# M-LVDS_PHY.net
KiCad netlist of a schematic drawn in Altium Designer
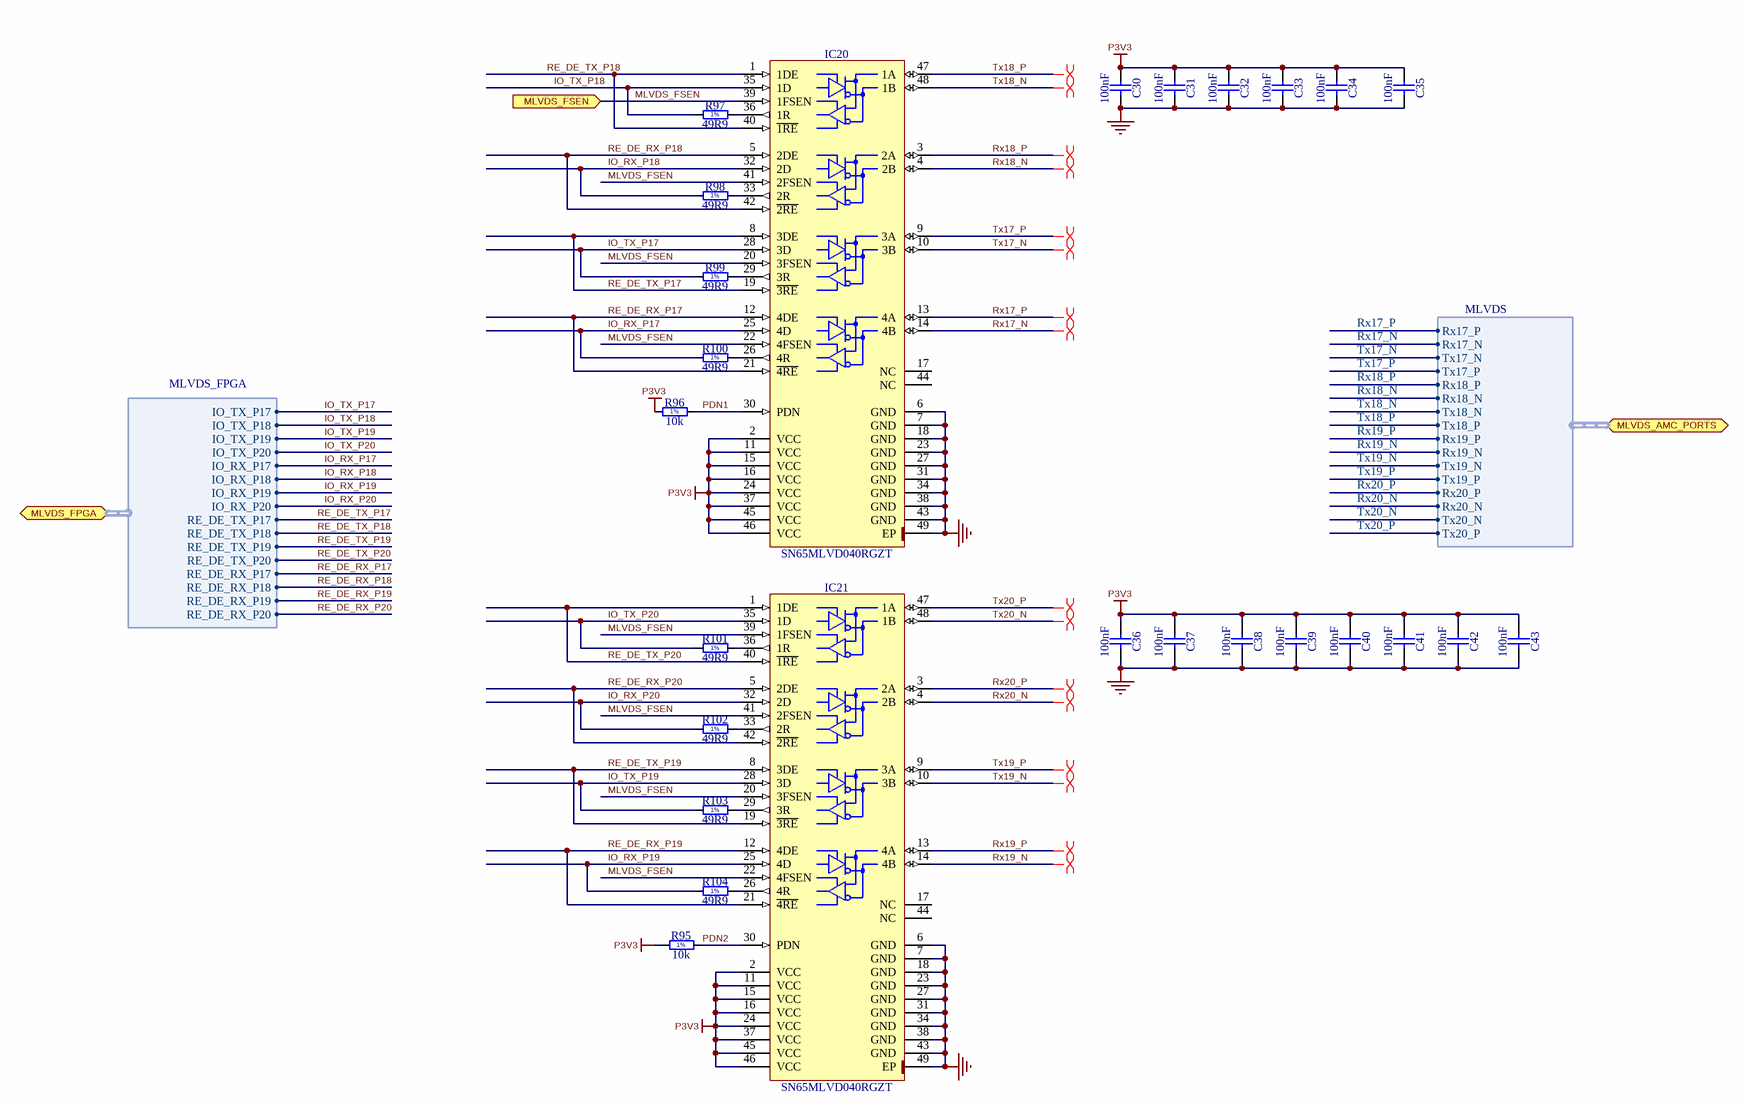
[diagram p0: M-LVDS_PHY.SchDoc]

(export (version "E")
  (design (tool "Eeschema 10.0.6"))
  (components
    (comp (ref "C30")
      (value "100nF")
      (footprint "CAPC0603X33N")
      (description "Non-polarised capacitor")
      (fields
        (field (name "MANUFACTURER PART NUMBER") "CC0201_100NF_6.3V_10%_X5R")
        (field (name "MANUFACTURER") "GENERIC")
        (field (name "AUTHOR") "CERN DEM JLC")
      )
      (libsource (lib "Capacitors") (part "Capacitor - non polarized"))
    )
    (comp (ref "C31")
      (value "100nF")
      (footprint "CAPC0603X33N")
      (description "Non-polarised capacitor")
      (fields
        (field (name "MANUFACTURER PART NUMBER") "CC0201_100NF_6.3V_10%_X5R")
        (field (name "MANUFACTURER") "GENERIC")
        (field (name "AUTHOR") "CERN DEM JLC")
      )
      (libsource (lib "Capacitors") (part "Capacitor - non polarized"))
    )
    (comp (ref "C32")
      (value "100nF")
      (footprint "CAPC0603X33N")
      (description "Non-polarised capacitor")
      (fields
        (field (name "MANUFACTURER PART NUMBER") "CC0201_100NF_6.3V_10%_X5R")
        (field (name "MANUFACTURER") "GENERIC")
        (field (name "AUTHOR") "CERN DEM JLC")
      )
      (libsource (lib "Capacitors") (part "Capacitor - non polarized"))
    )
    (comp (ref "C33")
      (value "100nF")
      (footprint "CAPC0603X33N")
      (description "Non-polarised capacitor")
      (fields
        (field (name "MANUFACTURER PART NUMBER") "CC0201_100NF_6.3V_10%_X5R")
        (field (name "MANUFACTURER") "GENERIC")
        (field (name "AUTHOR") "CERN DEM JLC")
      )
      (libsource (lib "Capacitors") (part "Capacitor - non polarized"))
    )
    (comp (ref "C34")
      (value "100nF")
      (footprint "CAPC0603X33N")
      (description "Non-polarised capacitor")
      (fields
        (field (name "MANUFACTURER PART NUMBER") "CC0201_100NF_6.3V_10%_X5R")
        (field (name "MANUFACTURER") "GENERIC")
        (field (name "AUTHOR") "CERN DEM JLC")
      )
      (libsource (lib "Capacitors") (part "Capacitor - non polarized"))
    )
    (comp (ref "C35")
      (value "100nF")
      (footprint "CAPC0603X33N")
      (description "Non-polarised capacitor")
      (fields
        (field (name "MANUFACTURER PART NUMBER") "CC0201_100NF_6.3V_10%_X5R")
        (field (name "MANUFACTURER") "GENERIC")
        (field (name "AUTHOR") "CERN DEM JLC")
      )
      (libsource (lib "Capacitors") (part "Capacitor - non polarized"))
    )
    (comp (ref "C36")
      (value "100nF")
      (footprint "CAPC0603X33N")
      (description "Non-polarised capacitor")
      (fields
        (field (name "MANUFACTURER PART NUMBER") "CC0201_100NF_6.3V_10%_X5R")
        (field (name "MANUFACTURER") "GENERIC")
        (field (name "AUTHOR") "CERN DEM JLC")
      )
      (libsource (lib "Capacitors") (part "Capacitor - non polarized"))
    )
    (comp (ref "C37")
      (value "100nF")
      (footprint "CAPC0603X33N")
      (description "Non-polarised capacitor")
      (fields
        (field (name "MANUFACTURER PART NUMBER") "CC0201_100NF_6.3V_10%_X5R")
        (field (name "MANUFACTURER") "GENERIC")
        (field (name "AUTHOR") "CERN DEM JLC")
      )
      (libsource (lib "Capacitors") (part "Capacitor - non polarized"))
    )
    (comp (ref "C38")
      (value "100nF")
      (footprint "CAPC0603X33N")
      (description "Non-polarised capacitor")
      (fields
        (field (name "MANUFACTURER PART NUMBER") "CC0201_100NF_6.3V_10%_X5R")
        (field (name "MANUFACTURER") "GENERIC")
        (field (name "AUTHOR") "CERN DEM JLC")
      )
      (libsource (lib "Capacitors") (part "Capacitor - non polarized"))
    )
    (comp (ref "C39")
      (value "100nF")
      (footprint "CAPC0603X33N")
      (description "Non-polarised capacitor")
      (fields
        (field (name "MANUFACTURER PART NUMBER") "CC0201_100NF_6.3V_10%_X5R")
        (field (name "MANUFACTURER") "GENERIC")
        (field (name "AUTHOR") "CERN DEM JLC")
      )
      (libsource (lib "Capacitors") (part "Capacitor - non polarized"))
    )
    (comp (ref "C40")
      (value "100nF")
      (footprint "CAPC0603X33N")
      (description "Non-polarised capacitor")
      (fields
        (field (name "MANUFACTURER PART NUMBER") "CC0201_100NF_6.3V_10%_X5R")
        (field (name "MANUFACTURER") "GENERIC")
        (field (name "AUTHOR") "CERN DEM JLC")
      )
      (libsource (lib "Capacitors") (part "Capacitor - non polarized"))
    )
    (comp (ref "C41")
      (value "100nF")
      (footprint "CAPC0603X33N")
      (description "Non-polarised capacitor")
      (fields
        (field (name "MANUFACTURER PART NUMBER") "CC0201_100NF_6.3V_10%_X5R")
        (field (name "MANUFACTURER") "GENERIC")
        (field (name "AUTHOR") "CERN DEM JLC")
      )
      (libsource (lib "Capacitors") (part "Capacitor - non polarized"))
    )
    (comp (ref "C42")
      (value "100nF")
      (footprint "CAPC0603X33N")
      (description "Non-polarised capacitor")
      (fields
        (field (name "MANUFACTURER PART NUMBER") "CC0201_100NF_6.3V_10%_X5R")
        (field (name "MANUFACTURER") "GENERIC")
        (field (name "AUTHOR") "CERN DEM JLC")
      )
      (libsource (lib "Capacitors") (part "Capacitor - non polarized"))
    )
    (comp (ref "C43")
      (value "100nF")
      (footprint "CAPC0603X33N")
      (description "Non-polarised capacitor")
      (fields
        (field (name "MANUFACTURER PART NUMBER") "CC0201_100NF_6.3V_10%_X5R")
        (field (name "MANUFACTURER") "GENERIC")
        (field (name "AUTHOR") "CERN DEM JLC")
      )
      (libsource (lib "Capacitors") (part "Capacitor - non polarized"))
    )
    (comp (ref "IC20")
      (value "SN65MLVD040RGZT")
      (footprint "QFN50P700X700X100-49N-S420")
      (description "4-Channel Half-Duplex M-LVDS Line Transceiver")
      (fields (field (name "MANUFACTURER") "TEXAS INSTRUMENTS") (field (name "AUTHOR") "CERN DEM JLC"))
      (libsource (lib "ICs And Semiconductors") (part "SN65MLVD040"))
    )
    (comp (ref "IC21")
      (value "SN65MLVD040RGZT")
      (footprint "QFN50P700X700X100-49N-S420")
      (description "4-Channel Half-Duplex M-LVDS Line Transceiver")
      (fields (field (name "MANUFACTURER") "TEXAS INSTRUMENTS") (field (name "AUTHOR") "CERN DEM JLC"))
      (libsource (lib "ICs And Semiconductors") (part "SN65MLVD040"))
    )
    (comp (ref "R95")
      (value "10k")
      (footprint "RESC1005X40N")
      (description "Resistor - 1%")
      (fields
        (field (name "MANUFACTURER PART NUMBER") "R0402_10K_1%_0.0625W_100PPM")
        (field (name "MANUFACTURER") "GENERIC")
        (field (name "AUTHOR") "CERN DEM JLC")
      )
      (libsource (lib "Resistors") (part "Resistor - 1%"))
    )
    (comp (ref "R96")
      (value "10k")
      (footprint "RESC1005X40N")
      (description "Resistor - 1%")
      (fields
        (field (name "MANUFACTURER PART NUMBER") "R0402_10K_1%_0.0625W_100PPM")
        (field (name "MANUFACTURER") "GENERIC")
        (field (name "AUTHOR") "CERN DEM JLC")
      )
      (libsource (lib "Resistors") (part "Resistor - 1%"))
    )
    (comp (ref "R97")
      (value "49R9")
      (footprint "RESC1005X40N")
      (description "Resistor - 1%")
      (fields
        (field (name "MANUFACTURER PART NUMBER") "R0402_49R9_1%_0.0625W_100PPM")
        (field (name "MANUFACTURER") "GENERIC")
        (field (name "AUTHOR") "CERN DEM JLC")
      )
      (libsource (lib "Resistors") (part "Resistor - 1%"))
    )
    (comp (ref "R98")
      (value "49R9")
      (footprint "RESC1005X40N")
      (description "Resistor - 1%")
      (fields
        (field (name "MANUFACTURER PART NUMBER") "R0402_49R9_1%_0.0625W_100PPM")
        (field (name "MANUFACTURER") "GENERIC")
        (field (name "AUTHOR") "CERN DEM JLC")
      )
      (libsource (lib "Resistors") (part "Resistor - 1%"))
    )
    (comp (ref "R99")
      (value "49R9")
      (footprint "RESC1005X40N")
      (description "Resistor - 1%")
      (fields
        (field (name "MANUFACTURER PART NUMBER") "R0402_49R9_1%_0.0625W_100PPM")
        (field (name "MANUFACTURER") "GENERIC")
        (field (name "AUTHOR") "CERN DEM JLC")
      )
      (libsource (lib "Resistors") (part "Resistor - 1%"))
    )
    (comp (ref "R100")
      (value "49R9")
      (footprint "RESC1005X40N")
      (description "Resistor - 1%")
      (fields
        (field (name "MANUFACTURER PART NUMBER") "R0402_49R9_1%_0.0625W_100PPM")
        (field (name "MANUFACTURER") "GENERIC")
        (field (name "AUTHOR") "CERN DEM JLC")
      )
      (libsource (lib "Resistors") (part "Resistor - 1%"))
    )
    (comp (ref "R101")
      (value "49R9")
      (footprint "RESC1005X40N")
      (description "Resistor - 1%")
      (fields
        (field (name "MANUFACTURER PART NUMBER") "R0402_49R9_1%_0.0625W_100PPM")
        (field (name "MANUFACTURER") "GENERIC")
        (field (name "AUTHOR") "CERN DEM JLC")
      )
      (libsource (lib "Resistors") (part "Resistor - 1%"))
    )
    (comp (ref "R102")
      (value "49R9")
      (footprint "RESC1005X40N")
      (description "Resistor - 1%")
      (fields
        (field (name "MANUFACTURER PART NUMBER") "R0402_49R9_1%_0.0625W_100PPM")
        (field (name "MANUFACTURER") "GENERIC")
        (field (name "AUTHOR") "CERN DEM JLC")
      )
      (libsource (lib "Resistors") (part "Resistor - 1%"))
    )
    (comp (ref "R103")
      (value "49R9")
      (footprint "RESC1005X40N")
      (description "Resistor - 1%")
      (fields
        (field (name "MANUFACTURER PART NUMBER") "R0402_49R9_1%_0.0625W_100PPM")
        (field (name "MANUFACTURER") "GENERIC")
        (field (name "AUTHOR") "CERN DEM JLC")
      )
      (libsource (lib "Resistors") (part "Resistor - 1%"))
    )
    (comp (ref "R104")
      (value "49R9")
      (footprint "RESC1005X40N")
      (description "Resistor - 1%")
      (fields
        (field (name "MANUFACTURER PART NUMBER") "R0402_49R9_1%_0.0625W_100PPM")
        (field (name "MANUFACTURER") "GENERIC")
        (field (name "AUTHOR") "CERN DEM JLC")
      )
      (libsource (lib "Resistors") (part "Resistor - 1%"))
    )
  )
  (nets
    (net (code "3") (name "/IO_RX_P17") (class "Default")
      (node (ref "IC20") (pin "25") (pinfunction "4D_25") (pintype "input"))
      (node (ref "R100") (pin "1") (pinfunction "1_1") (pintype "passive"))
    )
    (net (code "4") (name "/IO_RX_P18") (class "Default")
      (node (ref "IC20") (pin "32") (pinfunction "2D_32") (pintype "input"))
      (node (ref "R98") (pin "1") (pinfunction "1_1") (pintype "passive"))
    )
    (net (code "5") (name "/IO_RX_P19") (class "Default")
      (node (ref "IC21") (pin "25") (pinfunction "4D_25") (pintype "input"))
      (node (ref "R104") (pin "1") (pinfunction "1_1") (pintype "passive"))
    )
    (net (code "6") (name "/IO_RX_P20") (class "Default")
      (node (ref "IC21") (pin "32") (pinfunction "2D_32") (pintype "input"))
      (node (ref "R102") (pin "1") (pinfunction "1_1") (pintype "passive"))
    )
    (net (code "7") (name "/IO_TX_P17") (class "Default")
      (node (ref "IC20") (pin "28") (pinfunction "3D_28") (pintype "input"))
      (node (ref "R99") (pin "1") (pinfunction "1_1") (pintype "passive"))
    )
    (net (code "8") (name "/IO_TX_P18") (class "Default")
      (node (ref "IC20") (pin "35") (pinfunction "1D_35") (pintype "input"))
      (node (ref "R97") (pin "1") (pinfunction "1_1") (pintype "passive"))
    )
    (net (code "9") (name "/IO_TX_P19") (class "Default")
      (node (ref "IC21") (pin "28") (pinfunction "3D_28") (pintype "input"))
      (node (ref "R103") (pin "1") (pinfunction "1_1") (pintype "passive"))
    )
    (net (code "10") (name "/IO_TX_P20") (class "Default")
      (node (ref "IC21") (pin "35") (pinfunction "1D_35") (pintype "input"))
      (node (ref "R101") (pin "1") (pinfunction "1_1") (pintype "passive"))
    )
    (net (code "11") (name "/MLVDS_FSEN") (class "Default")
      (node (ref "IC20") (pin "20") (pinfunction "3FSEN_20") (pintype "input"))
      (node (ref "IC20") (pin "22") (pinfunction "4FSEN_22") (pintype "input"))
      (node (ref "IC20") (pin "39") (pinfunction "1FSEN_39") (pintype "input"))
      (node (ref "IC20") (pin "41") (pinfunction "2FSEN_41") (pintype "input"))
      (node (ref "IC21") (pin "20") (pinfunction "3FSEN_20") (pintype "input"))
      (node (ref "IC21") (pin "22") (pinfunction "4FSEN_22") (pintype "input"))
      (node (ref "IC21") (pin "39") (pinfunction "1FSEN_39") (pintype "input"))
      (node (ref "IC21") (pin "41") (pinfunction "2FSEN_41") (pintype "input"))
    )
    (net (code "12") (name "/PDN1") (class "Default")
      (node (ref "IC20") (pin "30") (pinfunction "PDN_30") (pintype "input"))
      (node (ref "R96") (pin "2") (pinfunction "2_2") (pintype "passive"))
    )
    (net (code "13") (name "/PDN2") (class "Default")
      (node (ref "IC21") (pin "30") (pinfunction "PDN_30") (pintype "input"))
      (node (ref "R95") (pin "2") (pinfunction "2_2") (pintype "passive"))
    )
    (net (code "14") (name "/RE_DE_RX_P17") (class "Default")
      (node (ref "IC20") (pin "12") (pinfunction "4DE_12") (pintype "input"))
      (node (ref "IC20") (pin "21") (pinfunction "~{4RE}_21") (pintype "input"))
    )
    (net (code "15") (name "/RE_DE_RX_P18") (class "Default")
      (node (ref "IC20") (pin "42") (pinfunction "~{2RE}_42") (pintype "input"))
      (node (ref "IC20") (pin "5") (pinfunction "2DE_5") (pintype "input"))
    )
    (net (code "16") (name "/RE_DE_RX_P19") (class "Default")
      (node (ref "IC21") (pin "12") (pinfunction "4DE_12") (pintype "input"))
      (node (ref "IC21") (pin "21") (pinfunction "~{4RE}_21") (pintype "input"))
    )
    (net (code "17") (name "/RE_DE_RX_P20") (class "Default")
      (node (ref "IC21") (pin "42") (pinfunction "~{2RE}_42") (pintype "input"))
      (node (ref "IC21") (pin "5") (pinfunction "2DE_5") (pintype "input"))
    )
    (net (code "18") (name "/RE_DE_TX_P17") (class "Default")
      (node (ref "IC20") (pin "19") (pinfunction "~{3RE}_19") (pintype "input"))
      (node (ref "IC20") (pin "8") (pinfunction "3DE_8") (pintype "input"))
    )
    (net (code "19") (name "/RE_DE_TX_P18") (class "Default")
      (node (ref "IC20") (pin "1") (pinfunction "1DE_1") (pintype "input"))
      (node (ref "IC20") (pin "40") (pinfunction "~{1RE}_40") (pintype "input"))
    )
    (net (code "20") (name "/RE_DE_TX_P19") (class "Default")
      (node (ref "IC21") (pin "19") (pinfunction "~{3RE}_19") (pintype "input"))
      (node (ref "IC21") (pin "8") (pinfunction "3DE_8") (pintype "input"))
    )
    (net (code "21") (name "/RE_DE_TX_P20") (class "Default")
      (node (ref "IC21") (pin "1") (pinfunction "1DE_1") (pintype "input"))
      (node (ref "IC21") (pin "40") (pinfunction "~{1RE}_40") (pintype "input"))
    )
    (net (code "22") (name "/Rx17_N") (class "Default")
      (node (ref "IC20") (pin "14") (pinfunction "4B_14") (pintype "bidirectional"))
    )
    (net (code "23") (name "/Rx17_P") (class "Default")
      (node (ref "IC20") (pin "13") (pinfunction "4A_13") (pintype "bidirectional"))
    )
    (net (code "24") (name "/Rx18_N") (class "Default")
      (node (ref "IC20") (pin "4") (pinfunction "2B_4") (pintype "bidirectional"))
    )
    (net (code "25") (name "/Rx18_P") (class "Default")
      (node (ref "IC20") (pin "3") (pinfunction "2A_3") (pintype "bidirectional"))
    )
    (net (code "26") (name "/Rx19_N") (class "Default")
      (node (ref "IC21") (pin "14") (pinfunction "4B_14") (pintype "bidirectional"))
    )
    (net (code "27") (name "/Rx19_P") (class "Default")
      (node (ref "IC21") (pin "13") (pinfunction "4A_13") (pintype "bidirectional"))
    )
    (net (code "28") (name "/Rx20_N") (class "Default")
      (node (ref "IC21") (pin "4") (pinfunction "2B_4") (pintype "bidirectional"))
    )
    (net (code "29") (name "/Rx20_P") (class "Default")
      (node (ref "IC21") (pin "3") (pinfunction "2A_3") (pintype "bidirectional"))
    )
    (net (code "30") (name "/Tx17_N") (class "Default")
      (node (ref "IC20") (pin "10") (pinfunction "3B_10") (pintype "bidirectional"))
    )
    (net (code "31") (name "/Tx17_P") (class "Default")
      (node (ref "IC20") (pin "9") (pinfunction "3A_9") (pintype "bidirectional"))
    )
    (net (code "32") (name "/Tx18_N") (class "Default")
      (node (ref "IC20") (pin "48") (pinfunction "1B_48") (pintype "bidirectional"))
    )
    (net (code "33") (name "/Tx18_P") (class "Default")
      (node (ref "IC20") (pin "47") (pinfunction "1A_47") (pintype "bidirectional"))
    )
    (net (code "34") (name "/Tx19_N") (class "Default")
      (node (ref "IC21") (pin "10") (pinfunction "3B_10") (pintype "bidirectional"))
    )
    (net (code "35") (name "/Tx19_P") (class "Default")
      (node (ref "IC21") (pin "9") (pinfunction "3A_9") (pintype "bidirectional"))
    )
    (net (code "36") (name "/Tx20_N") (class "Default")
      (node (ref "IC21") (pin "48") (pinfunction "1B_48") (pintype "bidirectional"))
    )
    (net (code "37") (name "/Tx20_P") (class "Default")
      (node (ref "IC21") (pin "47") (pinfunction "1A_47") (pintype "bidirectional"))
    )
    (net (code "40") (name "GND") (class "Default")
      (node (ref "C30") (pin "2") (pinfunction "2_2") (pintype "passive"))
      (node (ref "C31") (pin "2") (pinfunction "2_2") (pintype "passive"))
      (node (ref "C32") (pin "2") (pinfunction "2_2") (pintype "passive"))
      (node (ref "C33") (pin "2") (pinfunction "2_2") (pintype "passive"))
      (node (ref "C34") (pin "2") (pinfunction "2_2") (pintype "passive"))
      (node (ref "C35") (pin "2") (pinfunction "2_2") (pintype "passive"))
      (node (ref "C36") (pin "2") (pinfunction "2_2") (pintype "passive"))
      (node (ref "C37") (pin "2") (pinfunction "2_2") (pintype "passive"))
      (node (ref "C38") (pin "2") (pinfunction "2_2") (pintype "passive"))
      (node (ref "C39") (pin "2") (pinfunction "2_2") (pintype "passive"))
      (node (ref "C40") (pin "2") (pinfunction "2_2") (pintype "passive"))
      (node (ref "C41") (pin "2") (pinfunction "2_2") (pintype "passive"))
      (node (ref "C42") (pin "2") (pinfunction "2_2") (pintype "passive"))
      (node (ref "C43") (pin "2") (pinfunction "2_2") (pintype "passive"))
      (node (ref "IC20") (pin "18") (pinfunction "GND_18") (pintype "power_in"))
      (node (ref "IC20") (pin "23") (pinfunction "GND_23") (pintype "power_in"))
      (node (ref "IC20") (pin "27") (pinfunction "GND_27") (pintype "power_in"))
      (node (ref "IC20") (pin "31") (pinfunction "GND_31") (pintype "power_in"))
      (node (ref "IC20") (pin "34") (pinfunction "GND_34") (pintype "power_in"))
      (node (ref "IC20") (pin "38") (pinfunction "GND_38") (pintype "power_in"))
      (node (ref "IC20") (pin "43") (pinfunction "GND_43") (pintype "power_in"))
      (node (ref "IC20") (pin "49") (pinfunction "EP_49") (pintype "power_in"))
      (node (ref "IC20") (pin "6") (pinfunction "GND_6") (pintype "power_in"))
      (node (ref "IC20") (pin "7") (pinfunction "GND_7") (pintype "power_in"))
      (node (ref "IC21") (pin "18") (pinfunction "GND_18") (pintype "power_in"))
      (node (ref "IC21") (pin "23") (pinfunction "GND_23") (pintype "power_in"))
      (node (ref "IC21") (pin "27") (pinfunction "GND_27") (pintype "power_in"))
      (node (ref "IC21") (pin "31") (pinfunction "GND_31") (pintype "power_in"))
      (node (ref "IC21") (pin "34") (pinfunction "GND_34") (pintype "power_in"))
      (node (ref "IC21") (pin "38") (pinfunction "GND_38") (pintype "power_in"))
      (node (ref "IC21") (pin "43") (pinfunction "GND_43") (pintype "power_in"))
      (node (ref "IC21") (pin "49") (pinfunction "EP_49") (pintype "power_in"))
      (node (ref "IC21") (pin "6") (pinfunction "GND_6") (pintype "power_in"))
      (node (ref "IC21") (pin "7") (pinfunction "GND_7") (pintype "power_in"))
    )
    (net (code "41") (name "Net-(IC20-1R)") (class "Default")
      (node (ref "IC20") (pin "36") (pinfunction "1R_36") (pintype "output"))
      (node (ref "R97") (pin "2") (pinfunction "2_2") (pintype "passive"))
    )
    (net (code "42") (name "Net-(IC20-2R)") (class "Default")
      (node (ref "IC20") (pin "33") (pinfunction "2R_33") (pintype "output"))
      (node (ref "R98") (pin "2") (pinfunction "2_2") (pintype "passive"))
    )
    (net (code "43") (name "Net-(IC20-3R)") (class "Default")
      (node (ref "IC20") (pin "29") (pinfunction "3R_29") (pintype "output"))
      (node (ref "R99") (pin "2") (pinfunction "2_2") (pintype "passive"))
    )
    (net (code "44") (name "Net-(IC20-4R)") (class "Default")
      (node (ref "IC20") (pin "26") (pinfunction "4R_26") (pintype "output"))
      (node (ref "R100") (pin "2") (pinfunction "2_2") (pintype "passive"))
    )
    (net (code "45") (name "Net-(IC21-1R)") (class "Default")
      (node (ref "IC21") (pin "36") (pinfunction "1R_36") (pintype "output"))
      (node (ref "R101") (pin "2") (pinfunction "2_2") (pintype "passive"))
    )
    (net (code "46") (name "Net-(IC21-2R)") (class "Default")
      (node (ref "IC21") (pin "33") (pinfunction "2R_33") (pintype "output"))
      (node (ref "R102") (pin "2") (pinfunction "2_2") (pintype "passive"))
    )
    (net (code "47") (name "Net-(IC21-3R)") (class "Default")
      (node (ref "IC21") (pin "29") (pinfunction "3R_29") (pintype "output"))
      (node (ref "R103") (pin "2") (pinfunction "2_2") (pintype "passive"))
    )
    (net (code "48") (name "Net-(IC21-4R)") (class "Default")
      (node (ref "IC21") (pin "26") (pinfunction "4R_26") (pintype "output"))
      (node (ref "R104") (pin "2") (pinfunction "2_2") (pintype "passive"))
    )
    (net (code "49") (name "P3V3") (class "Default")
      (node (ref "C30") (pin "1") (pinfunction "1_1") (pintype "passive"))
      (node (ref "C31") (pin "1") (pinfunction "1_1") (pintype "passive"))
      (node (ref "C32") (pin "1") (pinfunction "1_1") (pintype "passive"))
      (node (ref "C33") (pin "1") (pinfunction "1_1") (pintype "passive"))
      (node (ref "C34") (pin "1") (pinfunction "1_1") (pintype "passive"))
      (node (ref "C35") (pin "1") (pinfunction "1_1") (pintype "passive"))
      (node (ref "C36") (pin "1") (pinfunction "1_1") (pintype "passive"))
      (node (ref "C37") (pin "1") (pinfunction "1_1") (pintype "passive"))
      (node (ref "C38") (pin "1") (pinfunction "1_1") (pintype "passive"))
      (node (ref "C39") (pin "1") (pinfunction "1_1") (pintype "passive"))
      (node (ref "C40") (pin "1") (pinfunction "1_1") (pintype "passive"))
      (node (ref "C41") (pin "1") (pinfunction "1_1") (pintype "passive"))
      (node (ref "C42") (pin "1") (pinfunction "1_1") (pintype "passive"))
      (node (ref "C43") (pin "1") (pinfunction "1_1") (pintype "passive"))
      (node (ref "IC20") (pin "11") (pinfunction "VCC_11") (pintype "power_in"))
      (node (ref "IC20") (pin "15") (pinfunction "VCC_15") (pintype "power_in"))
      (node (ref "IC20") (pin "16") (pinfunction "VCC_16") (pintype "power_in"))
      (node (ref "IC20") (pin "2") (pinfunction "VCC_2") (pintype "power_in"))
      (node (ref "IC20") (pin "24") (pinfunction "VCC_24") (pintype "power_in"))
      (node (ref "IC20") (pin "37") (pinfunction "VCC_37") (pintype "power_in"))
      (node (ref "IC20") (pin "45") (pinfunction "VCC_45") (pintype "power_in"))
      (node (ref "IC20") (pin "46") (pinfunction "VCC_46") (pintype "power_in"))
      (node (ref "IC21") (pin "11") (pinfunction "VCC_11") (pintype "power_in"))
      (node (ref "IC21") (pin "15") (pinfunction "VCC_15") (pintype "power_in"))
      (node (ref "IC21") (pin "16") (pinfunction "VCC_16") (pintype "power_in"))
      (node (ref "IC21") (pin "2") (pinfunction "VCC_2") (pintype "power_in"))
      (node (ref "IC21") (pin "24") (pinfunction "VCC_24") (pintype "power_in"))
      (node (ref "IC21") (pin "37") (pinfunction "VCC_37") (pintype "power_in"))
      (node (ref "IC21") (pin "45") (pinfunction "VCC_45") (pintype "power_in"))
      (node (ref "IC21") (pin "46") (pinfunction "VCC_46") (pintype "power_in"))
      (node (ref "R95") (pin "1") (pinfunction "1_1") (pintype "passive"))
      (node (ref "R96") (pin "1") (pinfunction "1_1") (pintype "passive"))
    )
    (net (code "50") (name "unconnected-(IC20-NC-Pad17)") (class "Default")
      (node (ref "IC20") (pin "17") (pinfunction "NC_17") (pintype "passive"))
    )
    (net (code "51") (name "unconnected-(IC20-NC-Pad44)") (class "Default")
      (node (ref "IC20") (pin "44") (pinfunction "NC_44") (pintype "passive"))
    )
    (net (code "52") (name "unconnected-(IC21-NC-Pad17)") (class "Default")
      (node (ref "IC21") (pin "17") (pinfunction "NC_17") (pintype "passive"))
    )
    (net (code "53") (name "unconnected-(IC21-NC-Pad44)") (class "Default")
      (node (ref "IC21") (pin "44") (pinfunction "NC_44") (pintype "passive"))
    )
  )
)
